# main.net
KiCad netlist of a schematic drawn in EAGLE
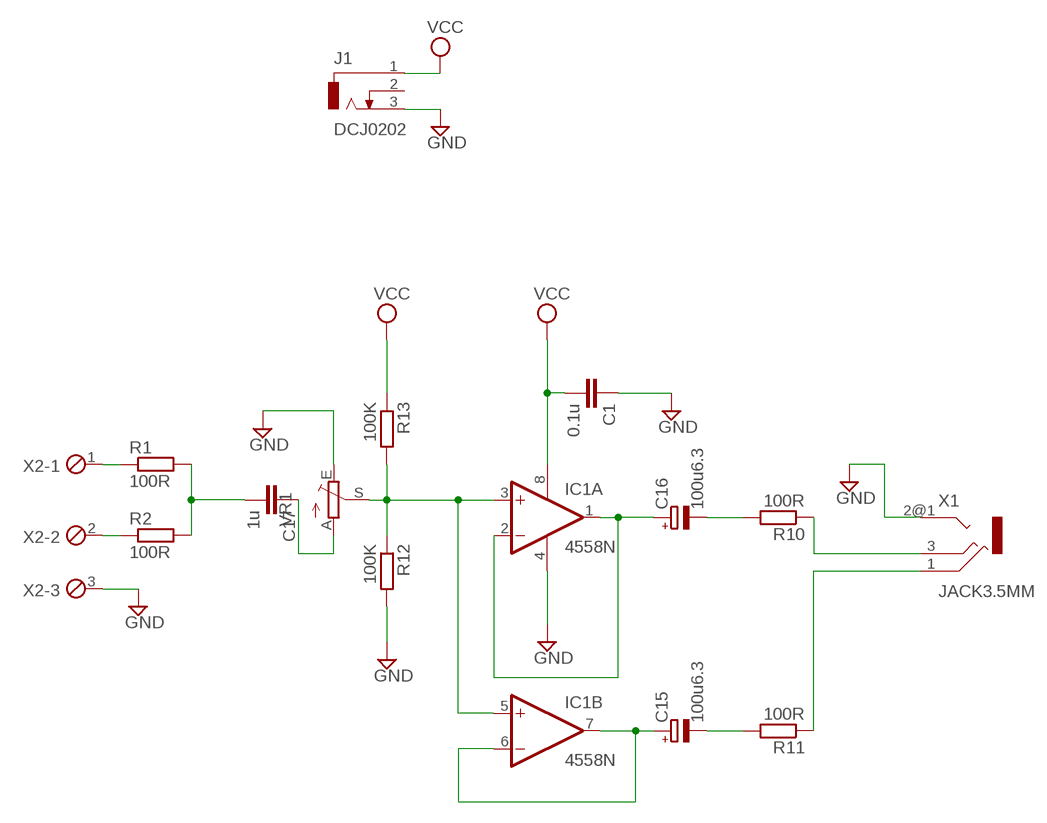
[diagram p0: schematic, sheet 1]

(export (version "E")
  (design (tool "Eeschema 10.0.6"))
  (components
    (comp (ref "C1")
      (value "0.1u")
      (footprint "eagle-import:C050-024X044")
      (libsource (lib "eagle-import") (part "C-EU050-024X044"))
    )
    (comp (ref "C15")
      (value "100u6.3")
      (footprint "eagle-import:TAP5-45")
      (libsource (lib "eagle-import") (part "CPOL-EUTAP5-45"))
    )
    (comp (ref "C16")
      (value "100u6.3")
      (footprint "eagle-import:TAP5-45")
      (libsource (lib "eagle-import") (part "CPOL-EUTAP5-45"))
    )
    (comp (ref "C17")
      (value "1u")
      (footprint "eagle-import:C050-024X044")
      (libsource (lib "eagle-import") (part "C-EU050-024X044"))
    )
    (comp (ref "IC1")
      (value "4558N")
      (footprint "eagle-import:DIP08")
      (libsource (lib "eagle-import") (part "4558N"))
    )
    (comp (ref "J1")
      (value "DCJ0202")
      (footprint "eagle-import:DCJ0202")
      (libsource (lib "eagle-import") (part "DCJ0202"))
    )
    (comp (ref "R1")
      (value "100R")
      (footprint "eagle-import:0207(1_4W)")
      (libsource (lib "eagle-import") (part "RESISTOR0207/12"))
    )
    (comp (ref "R2")
      (value "100R")
      (footprint "eagle-import:0207(1_4W)")
      (libsource (lib "eagle-import") (part "RESISTOR0207/12"))
    )
    (comp (ref "R10")
      (value "100R")
      (footprint "eagle-import:0207(1_4W)")
      (libsource (lib "eagle-import") (part "RESISTOR0207/12"))
    )
    (comp (ref "R11")
      (value "100R")
      (footprint "eagle-import:0207(1_4W)")
      (libsource (lib "eagle-import") (part "RESISTOR0207/12"))
    )
    (comp (ref "R12")
      (value "100K")
      (footprint "eagle-import:0207(1_4W)")
      (libsource (lib "eagle-import") (part "RESISTOR0207/12"))
    )
    (comp (ref "R13")
      (value "100K")
      (footprint "eagle-import:0207(1_4W)")
      (libsource (lib "eagle-import") (part "RESISTOR0207/12"))
    )
    (comp (ref "VR1")
      (value "KIT-TRIMPOTPOT_ST")
      (footprint "eagle-import:POT-ST")
      (libsource (lib "eagle-import") (part "KIT-TRIMPOTPOT_ST"))
    )
    (comp (ref "X1")
      (value "JACK3.5MM")
      (footprint "eagle-import:MJ-8435")
      (libsource (lib "eagle-import") (part "JACK3.5MM"))
    )
    (comp (ref "X2")
      (value "MPT3")
      (footprint "eagle-import:3POL254")
      (libsource (lib "eagle-import") (part "MPT3"))
    )
  )
  (nets
    (net (code "1") (name "GND") (class "Default")
      (node (ref "C1") (pin "1") (pinfunction "1_1") (pintype "passive"))
      (node (ref "IC1") (pin "4") (pinfunction "V-_4") (pintype "power_in"))
      (node (ref "J1") (pin "3") (pinfunction "3_3") (pintype "passive"))
      (node (ref "R12") (pin "2") (pinfunction "2_2") (pintype "passive"))
      (node (ref "VR1") (pin "E") (pinfunction "E_E") (pintype "passive"))
      (node (ref "X1") (pin "2@1") (pinfunction "2_2@1") (pintype "passive"))
      (node (ref "X2") (pin "3") (pinfunction "1_3") (pintype "passive"))
    )
    (net (code "2") (name "Net-(C15-Pad-)") (class "Default")
      (node (ref "C15") (pin "-") (pinfunction "-_-") (pintype "passive"))
      (node (ref "R11") (pin "2") (pinfunction "2_2") (pintype "passive"))
    )
    (net (code "3") (name "Net-(C16-Pad-)") (class "Default")
      (node (ref "C16") (pin "-") (pinfunction "-_-") (pintype "passive"))
      (node (ref "R10") (pin "2") (pinfunction "2_2") (pintype "passive"))
    )
    (net (code "4") (name "Net-(C17-Pad1)") (class "Default")
      (node (ref "C17") (pin "1") (pinfunction "1_1") (pintype "passive"))
      (node (ref "VR1") (pin "A") (pinfunction "A_A") (pintype "passive"))
    )
    (net (code "5") (name "Net-(C17-Pad2)") (class "Default")
      (node (ref "C17") (pin "2") (pinfunction "2_2") (pintype "passive"))
      (node (ref "R1") (pin "2") (pinfunction "2_2") (pintype "passive"))
      (node (ref "R2") (pin "2") (pinfunction "2_2") (pintype "passive"))
    )
    (net (code "6") (name "Net-(IC1A-+IN)") (class "Default")
      (node (ref "IC1") (pin "3") (pinfunction "+IN_3") (pintype "input"))
      (node (ref "IC1") (pin "5") (pinfunction "+IN_5") (pintype "input"))
      (node (ref "R12") (pin "1") (pinfunction "1_1") (pintype "passive"))
      (node (ref "R13") (pin "2") (pinfunction "2_2") (pintype "passive"))
      (node (ref "VR1") (pin "S") (pinfunction "S_S") (pintype "passive"))
    )
    (net (code "7") (name "Net-(IC1A--IN)") (class "Default")
      (node (ref "C16") (pin "+") (pinfunction "+_+") (pintype "passive"))
      (node (ref "IC1") (pin "1") (pinfunction "OUT_1") (pintype "output"))
      (node (ref "IC1") (pin "2") (pinfunction "-IN_2") (pintype "input"))
    )
    (net (code "8") (name "Net-(IC1B--IN)") (class "Default")
      (node (ref "C15") (pin "+") (pinfunction "+_+") (pintype "passive"))
      (node (ref "IC1") (pin "6") (pinfunction "-IN_6") (pintype "input"))
      (node (ref "IC1") (pin "7") (pinfunction "OUT_7") (pintype "output"))
    )
    (net (code "9") (name "Net-(R1-Pad1)") (class "Default")
      (node (ref "R1") (pin "1") (pinfunction "1_1") (pintype "passive"))
      (node (ref "X2") (pin "1") (pinfunction "1_1") (pintype "passive"))
    )
    (net (code "10") (name "Net-(R10-Pad1)") (class "Default")
      (node (ref "R10") (pin "1") (pinfunction "1_1") (pintype "passive"))
      (node (ref "X1") (pin "3") (pinfunction "3_3") (pintype "passive"))
    )
    (net (code "11") (name "Net-(R11-Pad1)") (class "Default")
      (node (ref "R11") (pin "1") (pinfunction "1_1") (pintype "passive"))
      (node (ref "X1") (pin "1") (pinfunction "1_1") (pintype "passive"))
    )
    (net (code "12") (name "Net-(X2B-1)") (class "Default")
      (node (ref "R2") (pin "1") (pinfunction "1_1") (pintype "passive"))
      (node (ref "X2") (pin "2") (pinfunction "1_2") (pintype "passive"))
    )
    (net (code "13") (name "VCC") (class "Default")
      (node (ref "C1") (pin "2") (pinfunction "2_2") (pintype "passive"))
      (node (ref "IC1") (pin "8") (pinfunction "V+_8") (pintype "power_in"))
      (node (ref "J1") (pin "1") (pinfunction "1_1") (pintype "passive"))
      (node (ref "R13") (pin "1") (pinfunction "1_1") (pintype "passive"))
    )
    (net (code "14") (name "unconnected-(J1-Pad2)") (class "Default")
      (node (ref "J1") (pin "2") (pinfunction "2_2") (pintype "passive"))
    )
    (net (code "15") (name "unconnected-(X1-2-Pad2@2)") (class "Default")
      (node (ref "X1") (pin "2@2") (pinfunction "2_2@2") (pintype "passive"))
    )
  )
)
